# Drivers.net
KiCad netlist of a schematic drawn in EAGLE
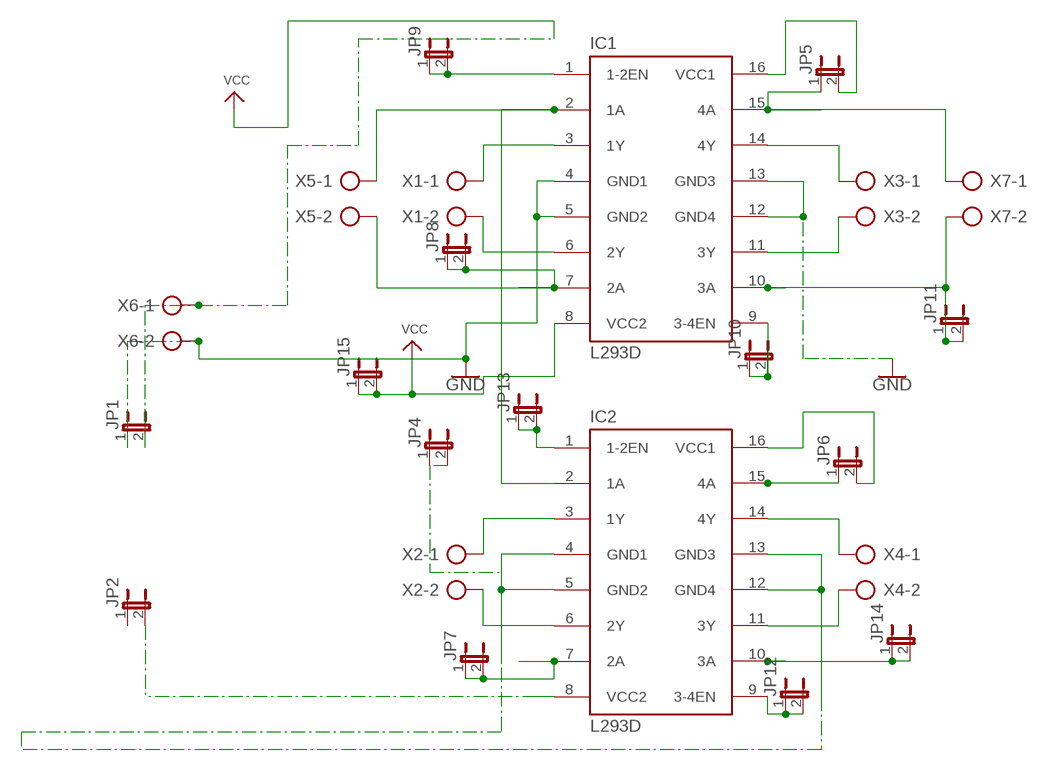
[diagram p0: schematic, sheet 1]

(export (version "E")
  (design (tool "Eeschema 10.0.6"))
  (components
    (comp (ref "IC1")
      (value "L293D")
      (footprint "eagle-import:DIL16")
      (libsource (lib "eagle-import") (part "L293D"))
    )
    (comp (ref "IC2")
      (value "L293D")
      (footprint "eagle-import:DIL16")
      (libsource (lib "eagle-import") (part "L293D"))
    )
    (comp (ref "JP1")
      (value "JP1E")
      (footprint "eagle-import:JP1")
      (libsource (lib "eagle-import") (part "JP1E"))
    )
    (comp (ref "JP2")
      (value "JP1E")
      (footprint "eagle-import:JP1")
      (libsource (lib "eagle-import") (part "JP1E"))
    )
    (comp (ref "JP4")
      (value "JP1E")
      (footprint "eagle-import:JP1")
      (libsource (lib "eagle-import") (part "JP1E"))
    )
    (comp (ref "JP5")
      (value "JP1E")
      (footprint "eagle-import:JP1")
      (libsource (lib "eagle-import") (part "JP1E"))
    )
    (comp (ref "JP6")
      (value "JP1E")
      (footprint "eagle-import:JP1")
      (libsource (lib "eagle-import") (part "JP1E"))
    )
    (comp (ref "JP7")
      (value "JP1E")
      (footprint "eagle-import:JP1")
      (libsource (lib "eagle-import") (part "JP1E"))
    )
    (comp (ref "JP8")
      (value "JP1E")
      (footprint "eagle-import:JP1")
      (libsource (lib "eagle-import") (part "JP1E"))
    )
    (comp (ref "JP9")
      (value "JP1E")
      (footprint "eagle-import:JP1")
      (libsource (lib "eagle-import") (part "JP1E"))
    )
    (comp (ref "JP10")
      (value "JP1E")
      (footprint "eagle-import:JP1")
      (libsource (lib "eagle-import") (part "JP1E"))
    )
    (comp (ref "JP11")
      (value "JP1E")
      (footprint "eagle-import:JP1")
      (libsource (lib "eagle-import") (part "JP1E"))
    )
    (comp (ref "JP12")
      (value "JP1E")
      (footprint "eagle-import:JP1")
      (libsource (lib "eagle-import") (part "JP1E"))
    )
    (comp (ref "JP13")
      (value "JP1E")
      (footprint "eagle-import:JP1")
      (libsource (lib "eagle-import") (part "JP1E"))
    )
    (comp (ref "JP14")
      (value "JP1E")
      (footprint "eagle-import:JP1")
      (libsource (lib "eagle-import") (part "JP1E"))
    )
    (comp (ref "JP15")
      (value "JP1E")
      (footprint "eagle-import:JP1")
      (libsource (lib "eagle-import") (part "JP1E"))
    )
    (comp (ref "X1")
      (value "AK500/2-H")
      (footprint "eagle-import:AK500_2-H")
      (libsource (lib "eagle-import") (part "AK500/2-H"))
    )
    (comp (ref "X2")
      (value "AK500/2-H")
      (footprint "eagle-import:AK500_2-H")
      (libsource (lib "eagle-import") (part "AK500/2-H"))
    )
    (comp (ref "X3")
      (value "AK500/2-H")
      (footprint "eagle-import:AK500_2-H")
      (libsource (lib "eagle-import") (part "AK500/2-H"))
    )
    (comp (ref "X4")
      (value "AK500/2-H")
      (footprint "eagle-import:AK500_2-H")
      (libsource (lib "eagle-import") (part "AK500/2-H"))
    )
    (comp (ref "X5")
      (value "AK500/2-H")
      (footprint "eagle-import:AK500_2-H")
      (libsource (lib "eagle-import") (part "AK500/2-H"))
    )
    (comp (ref "X6")
      (value "AK500/2-H")
      (footprint "eagle-import:AK500_2-H")
      (libsource (lib "eagle-import") (part "AK500/2-H"))
    )
    (comp (ref "X7")
      (value "AK500/2-H")
      (footprint "eagle-import:AK500_2-H")
      (libsource (lib "eagle-import") (part "AK500/2-H"))
    )
  )
  (nets
    (net (code "1") (name "GND") (class "Default")
      (node (ref "IC1") (pin "12") (pinfunction "GND4_12") (pintype "power_in"))
      (node (ref "IC1") (pin "13") (pinfunction "GND3_13") (pintype "power_in"))
      (node (ref "IC1") (pin "4") (pinfunction "GND1_4") (pintype "power_in"))
      (node (ref "IC1") (pin "5") (pinfunction "GND2_5") (pintype "power_in"))
      (node (ref "JP1") (pin "1") (pinfunction "1_1") (pintype "passive"))
      (node (ref "X6") (pin "2") (pinfunction "KL_2") (pintype "passive"))
    )
    (net (code "2") (name "Net-(IC1-1-2EN)") (class "Default")
      (node (ref "IC1") (pin "1") (pinfunction "1-2EN_1") (pintype "input"))
      (node (ref "JP9") (pin "1") (pinfunction "1_1") (pintype "passive"))
      (node (ref "JP9") (pin "2") (pinfunction "2_2") (pintype "passive"))
    )
    (net (code "3") (name "Net-(IC1-1A)") (class "Default")
      (node (ref "IC1") (pin "2") (pinfunction "1A_2") (pintype "input"))
      (node (ref "IC2") (pin "2") (pinfunction "1A_2") (pintype "input"))
      (node (ref "X5") (pin "1") (pinfunction "KL_1") (pintype "passive"))
    )
    (net (code "4") (name "Net-(IC1-1Y)") (class "Default")
      (node (ref "IC1") (pin "3") (pinfunction "1Y_3") (pintype "output"))
      (node (ref "X1") (pin "1") (pinfunction "KL_1") (pintype "passive"))
    )
    (net (code "5") (name "Net-(IC1-2A)") (class "Default")
      (node (ref "IC1") (pin "7") (pinfunction "2A_7") (pintype "input"))
      (node (ref "JP8") (pin "1") (pinfunction "1_1") (pintype "passive"))
      (node (ref "JP8") (pin "2") (pinfunction "2_2") (pintype "passive"))
      (node (ref "X5") (pin "2") (pinfunction "KL_2") (pintype "passive"))
    )
    (net (code "6") (name "Net-(IC1-2Y)") (class "Default")
      (node (ref "IC1") (pin "6") (pinfunction "2Y_6") (pintype "output"))
      (node (ref "X1") (pin "2") (pinfunction "KL_2") (pintype "passive"))
    )
    (net (code "7") (name "Net-(IC1-3-4EN)") (class "Default")
      (node (ref "IC1") (pin "9") (pinfunction "3-4EN_9") (pintype "input"))
      (node (ref "JP10") (pin "1") (pinfunction "1_1") (pintype "passive"))
      (node (ref "JP10") (pin "2") (pinfunction "2_2") (pintype "passive"))
    )
    (net (code "8") (name "Net-(IC1-3A)") (class "Default")
      (node (ref "IC1") (pin "10") (pinfunction "3A_10") (pintype "input"))
      (node (ref "JP11") (pin "1") (pinfunction "1_1") (pintype "passive"))
      (node (ref "JP11") (pin "2") (pinfunction "2_2") (pintype "passive"))
      (node (ref "X7") (pin "2") (pinfunction "KL_2") (pintype "passive"))
    )
    (net (code "9") (name "Net-(IC1-3Y)") (class "Default")
      (node (ref "IC1") (pin "11") (pinfunction "3Y_11") (pintype "output"))
      (node (ref "X3") (pin "2") (pinfunction "KL_2") (pintype "passive"))
    )
    (net (code "10") (name "Net-(IC1-4A)") (class "Default")
      (node (ref "IC1") (pin "15") (pinfunction "4A_15") (pintype "input"))
      (node (ref "JP5") (pin "1") (pinfunction "1_1") (pintype "passive"))
      (node (ref "X7") (pin "1") (pinfunction "KL_1") (pintype "passive"))
    )
    (net (code "11") (name "Net-(IC1-4Y)") (class "Default")
      (node (ref "IC1") (pin "14") (pinfunction "4Y_14") (pintype "output"))
      (node (ref "X3") (pin "1") (pinfunction "KL_1") (pintype "passive"))
    )
    (net (code "12") (name "Net-(IC1-VCC1)") (class "Default")
      (node (ref "IC1") (pin "16") (pinfunction "VCC1_16") (pintype "power_in"))
      (node (ref "JP5") (pin "2") (pinfunction "2_2") (pintype "passive"))
    )
    (net (code "13") (name "Net-(IC2-1-2EN)") (class "Default")
      (node (ref "IC2") (pin "1") (pinfunction "1-2EN_1") (pintype "input"))
      (node (ref "JP13") (pin "1") (pinfunction "1_1") (pintype "passive"))
      (node (ref "JP13") (pin "2") (pinfunction "2_2") (pintype "passive"))
    )
    (net (code "14") (name "Net-(IC2-1Y)") (class "Default")
      (node (ref "IC2") (pin "3") (pinfunction "1Y_3") (pintype "output"))
      (node (ref "X2") (pin "1") (pinfunction "KL_1") (pintype "passive"))
    )
    (net (code "15") (name "Net-(IC2-2A)") (class "Default")
      (node (ref "IC2") (pin "7") (pinfunction "2A_7") (pintype "input"))
      (node (ref "JP7") (pin "1") (pinfunction "1_1") (pintype "passive"))
      (node (ref "JP7") (pin "2") (pinfunction "2_2") (pintype "passive"))
    )
    (net (code "16") (name "Net-(IC2-2Y)") (class "Default")
      (node (ref "IC2") (pin "6") (pinfunction "2Y_6") (pintype "output"))
      (node (ref "X2") (pin "2") (pinfunction "KL_2") (pintype "passive"))
    )
    (net (code "17") (name "Net-(IC2-3-4EN)") (class "Default")
      (node (ref "IC2") (pin "9") (pinfunction "3-4EN_9") (pintype "input"))
      (node (ref "JP12") (pin "1") (pinfunction "1_1") (pintype "passive"))
      (node (ref "JP12") (pin "2") (pinfunction "2_2") (pintype "passive"))
    )
    (net (code "18") (name "Net-(IC2-3A)") (class "Default")
      (node (ref "IC2") (pin "10") (pinfunction "3A_10") (pintype "input"))
      (node (ref "JP14") (pin "1") (pinfunction "1_1") (pintype "passive"))
      (node (ref "JP14") (pin "2") (pinfunction "2_2") (pintype "passive"))
    )
    (net (code "19") (name "Net-(IC2-3Y)") (class "Default")
      (node (ref "IC2") (pin "11") (pinfunction "3Y_11") (pintype "output"))
      (node (ref "X4") (pin "2") (pinfunction "KL_2") (pintype "passive"))
    )
    (net (code "20") (name "Net-(IC2-4A)") (class "Default")
      (node (ref "IC2") (pin "15") (pinfunction "4A_15") (pintype "input"))
      (node (ref "JP6") (pin "1") (pinfunction "1_1") (pintype "passive"))
    )
    (net (code "21") (name "Net-(IC2-4Y)") (class "Default")
      (node (ref "IC2") (pin "14") (pinfunction "4Y_14") (pintype "output"))
      (node (ref "X4") (pin "1") (pinfunction "KL_1") (pintype "passive"))
    )
    (net (code "22") (name "Net-(IC2-GND1)") (class "Default")
      (node (ref "IC2") (pin "12") (pinfunction "GND4_12") (pintype "power_in"))
      (node (ref "IC2") (pin "13") (pinfunction "GND3_13") (pintype "power_in"))
      (node (ref "IC2") (pin "4") (pinfunction "GND1_4") (pintype "power_in"))
      (node (ref "IC2") (pin "5") (pinfunction "GND2_5") (pintype "power_in"))
      (node (ref "JP4") (pin "1") (pinfunction "1_1") (pintype "passive"))
      (node (ref "JP4") (pin "2") (pinfunction "2_2") (pintype "passive"))
    )
    (net (code "23") (name "Net-(IC2-VCC1)") (class "Default")
      (node (ref "IC2") (pin "16") (pinfunction "VCC1_16") (pintype "power_in"))
      (node (ref "JP6") (pin "2") (pinfunction "2_2") (pintype "passive"))
    )
    (net (code "24") (name "Net-(IC2-VCC2)") (class "Default")
      (node (ref "IC2") (pin "8") (pinfunction "VCC2_8") (pintype "power_in"))
      (node (ref "JP2") (pin "2") (pinfunction "2_2") (pintype "passive"))
    )
    (net (code "25") (name "VCC") (class "Default")
      (node (ref "IC1") (pin "8") (pinfunction "VCC2_8") (pintype "power_in"))
      (node (ref "JP1") (pin "2") (pinfunction "2_2") (pintype "passive"))
      (node (ref "JP15") (pin "1") (pinfunction "1_1") (pintype "passive"))
      (node (ref "JP15") (pin "2") (pinfunction "2_2") (pintype "passive"))
      (node (ref "X6") (pin "1") (pinfunction "KL_1") (pintype "passive"))
    )
    (net (code "26") (name "unconnected-(JP2-Pad1)") (class "Default")
      (node (ref "JP2") (pin "1") (pinfunction "1_1") (pintype "passive"))
    )
  )
)
